# untitled.net
KiCad netlist of a schematic drawn in EAGLE
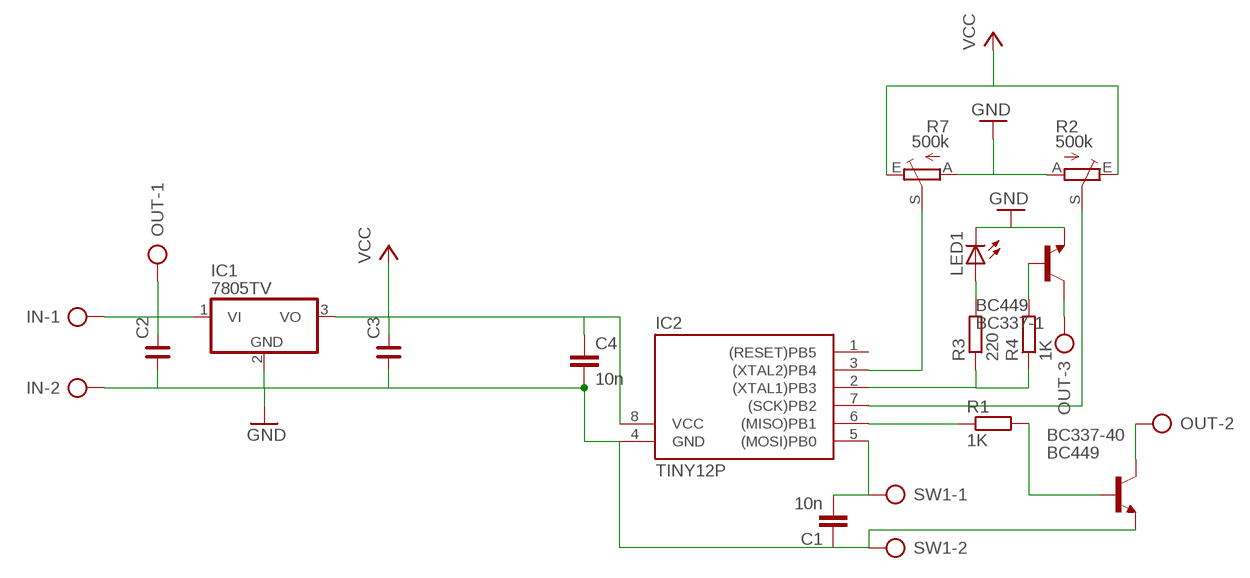
[diagram p0: schematic, sheet 1]

(export (version "E")
  (design (tool "Eeschema 10.0.6"))
  (components
    (comp (ref "BC337-1")
      (value "BC449")
      (footprint "eagle-import:TO92-EBC")
      (libsource (lib "eagle-import") (part "BC449"))
    )
    (comp (ref "BC337-40")
      (value "BC449")
      (footprint "eagle-import:TO92-EBC")
      (libsource (lib "eagle-import") (part "BC449"))
    )
    (comp (ref "C1")
      (value "10n")
      (footprint "eagle-import:C050-024X044")
      (libsource (lib "eagle-import") (part "C-EU050-024X044"))
    )
    (comp (ref "C2")
      (value "C_1206")
      (footprint "eagle-import:C1206")
      (libsource (lib "eagle-import") (part "C_1206"))
    )
    (comp (ref "C3")
      (value "C_1206")
      (footprint "eagle-import:C1206")
      (libsource (lib "eagle-import") (part "C_1206"))
    )
    (comp (ref "C4")
      (value "10n")
      (footprint "eagle-import:C050-024X044")
      (libsource (lib "eagle-import") (part "C-EU050-024X044"))
    )
    (comp (ref "IC1")
      (value "7805TV")
      (footprint "eagle-import:TO220V")
      (libsource (lib "eagle-import") (part "78TV05"))
    )
    (comp (ref "IC2")
      (value "TINY12P")
      (footprint "eagle-import:DIL08")
      (libsource (lib "eagle-import") (part "TINY12P"))
    )
    (comp (ref "IN")
      (value "AK500/2")
      (footprint "eagle-import:AK500_2")
      (libsource (lib "eagle-import") (part "AK500/2"))
    )
    (comp (ref "LED1")
      (value "LED3MM")
      (footprint "eagle-import:LED3MM")
      (libsource (lib "eagle-import") (part "LED3MM"))
    )
    (comp (ref "OUT")
      (value "AK500/3")
      (footprint "eagle-import:AK500_3")
      (libsource (lib "eagle-import") (part "AK500/3"))
    )
    (comp (ref "R1")
      (value "1K")
      (footprint "eagle-import:M1206")
      (libsource (lib "eagle-import") (part "R-EU_M1206"))
    )
    (comp (ref "R2")
      (value "500k")
      (footprint "eagle-import:CA6V")
      (libsource (lib "eagle-import") (part "TRIM_EU-CA6V"))
    )
    (comp (ref "R3")
      (value "220")
      (footprint "eagle-import:M1206")
      (libsource (lib "eagle-import") (part "R-EU_M1206"))
    )
    (comp (ref "R4")
      (value "1K")
      (footprint "eagle-import:M1206")
      (libsource (lib "eagle-import") (part "R-EU_M1206"))
    )
    (comp (ref "R7")
      (value "500k")
      (footprint "eagle-import:CA6V")
      (libsource (lib "eagle-import") (part "TRIM_EU-CA6V"))
    )
    (comp (ref "SW1")
      (value "AK500/2")
      (footprint "eagle-import:AK500_2")
      (libsource (lib "eagle-import") (part "AK500/2"))
    )
  )
  (nets
    (net (code "1") (name "GND") (class "Default")
      (node (ref "BC337-1") (pin "E") (pinfunction "E_E") (pintype "passive"))
      (node (ref "BC337-40") (pin "E") (pinfunction "E_E") (pintype "passive"))
      (node (ref "C1") (pin "1") (pinfunction "1_1") (pintype "passive"))
      (node (ref "C2") (pin "1") (pinfunction "1_1") (pintype "passive"))
      (node (ref "C3") (pin "1") (pinfunction "1_1") (pintype "passive"))
      (node (ref "C4") (pin "2") (pinfunction "2_2") (pintype "passive"))
      (node (ref "IC1") (pin "2") (pinfunction "GND_2") (pintype "passive"))
      (node (ref "IC2") (pin "4") (pinfunction "GND_4") (pintype "power_in"))
      (node (ref "IN") (pin "2") (pinfunction "KL_2") (pintype "passive"))
      (node (ref "LED1") (pin "K") (pinfunction "C_K") (pintype "passive"))
      (node (ref "R2") (pin "A") (pinfunction "A_A") (pintype "passive"))
      (node (ref "R7") (pin "A") (pinfunction "A_A") (pintype "passive"))
      (node (ref "SW1") (pin "2") (pinfunction "KL_2") (pintype "passive"))
    )
    (net (code "2") (name "Net-(BC337-1-PadB)") (class "Default")
      (node (ref "BC337-1") (pin "B") (pinfunction "B_B") (pintype "passive"))
      (node (ref "R4") (pin "2") (pinfunction "2_2") (pintype "passive"))
    )
    (net (code "3") (name "Net-(BC337-40-PadB)") (class "Default")
      (node (ref "BC337-40") (pin "B") (pinfunction "B_B") (pintype "passive"))
      (node (ref "R1") (pin "2") (pinfunction "2_2") (pintype "passive"))
    )
    (net (code "4") (name "Net-(IC1-VI)") (class "Default")
      (node (ref "C2") (pin "2") (pinfunction "2_2") (pintype "passive"))
      (node (ref "IC1") (pin "1") (pinfunction "VI_1") (pintype "input"))
      (node (ref "IN") (pin "1") (pinfunction "KL_1") (pintype "passive"))
      (node (ref "OUT") (pin "1") (pinfunction "KL_1") (pintype "passive"))
    )
    (net (code "5") (name "Net-(IC2-(MISO)PB1)") (class "Default")
      (node (ref "IC2") (pin "6") (pinfunction "(MISO)PB1_6") (pintype "bidirectional"))
      (node (ref "R1") (pin "1") (pinfunction "1_1") (pintype "passive"))
    )
    (net (code "6") (name "Net-(IC2-(MOSI)PB0)") (class "Default")
      (node (ref "C1") (pin "2") (pinfunction "2_2") (pintype "passive"))
      (node (ref "IC2") (pin "5") (pinfunction "(MOSI)PB0_5") (pintype "bidirectional"))
      (node (ref "SW1") (pin "1") (pinfunction "KL_1") (pintype "passive"))
    )
    (net (code "7") (name "Net-(IC2-(SCK)PB2)") (class "Default")
      (node (ref "IC2") (pin "7") (pinfunction "(SCK)PB2_7") (pintype "bidirectional"))
      (node (ref "R2") (pin "S") (pinfunction "S_S") (pintype "passive"))
    )
    (net (code "8") (name "Net-(IC2-(XTAL1)PB3)") (class "Default")
      (node (ref "IC2") (pin "2") (pinfunction "(XTAL1)PB3_2") (pintype "bidirectional"))
      (node (ref "R3") (pin "1") (pinfunction "1_1") (pintype "passive"))
      (node (ref "R4") (pin "1") (pinfunction "1_1") (pintype "passive"))
    )
    (net (code "9") (name "Net-(IC2-(XTAL2)PB4)") (class "Default")
      (node (ref "IC2") (pin "3") (pinfunction "(XTAL2)PB4_3") (pintype "bidirectional"))
      (node (ref "R7") (pin "S") (pinfunction "S_S") (pintype "passive"))
    )
    (net (code "10") (name "Net-(LED1-PadA)") (class "Default")
      (node (ref "LED1") (pin "A") (pinfunction "A_A") (pintype "passive"))
      (node (ref "R3") (pin "2") (pinfunction "2_2") (pintype "passive"))
    )
    (net (code "11") (name "Net-(OUTB-KL)") (class "Default")
      (node (ref "BC337-40") (pin "C") (pinfunction "C_C") (pintype "passive"))
      (node (ref "OUT") (pin "2") (pinfunction "KL_2") (pintype "passive"))
    )
    (net (code "12") (name "Net-(OUTC-KL)") (class "Default")
      (node (ref "BC337-1") (pin "C") (pinfunction "C_C") (pintype "passive"))
      (node (ref "OUT") (pin "3") (pinfunction "KL_3") (pintype "passive"))
    )
    (net (code "13") (name "VCC") (class "Default")
      (node (ref "C3") (pin "2") (pinfunction "2_2") (pintype "passive"))
      (node (ref "C4") (pin "1") (pinfunction "1_1") (pintype "passive"))
      (node (ref "IC1") (pin "3") (pinfunction "VO_3") (pintype "passive"))
      (node (ref "IC2") (pin "8") (pinfunction "VCC_8") (pintype "power_in"))
      (node (ref "R2") (pin "E") (pinfunction "E_E") (pintype "passive"))
      (node (ref "R7") (pin "E") (pinfunction "E_E") (pintype "passive"))
    )
    (net (code "14") (name "unconnected-(IC2-(RESET)PB5-Pad1)") (class "Default")
      (node (ref "IC2") (pin "1") (pinfunction "(RESET)PB5_1") (pintype "bidirectional"))
    )
  )
)
